# Eharvest.net
KiCad netlist of a schematic drawn in EAGLE
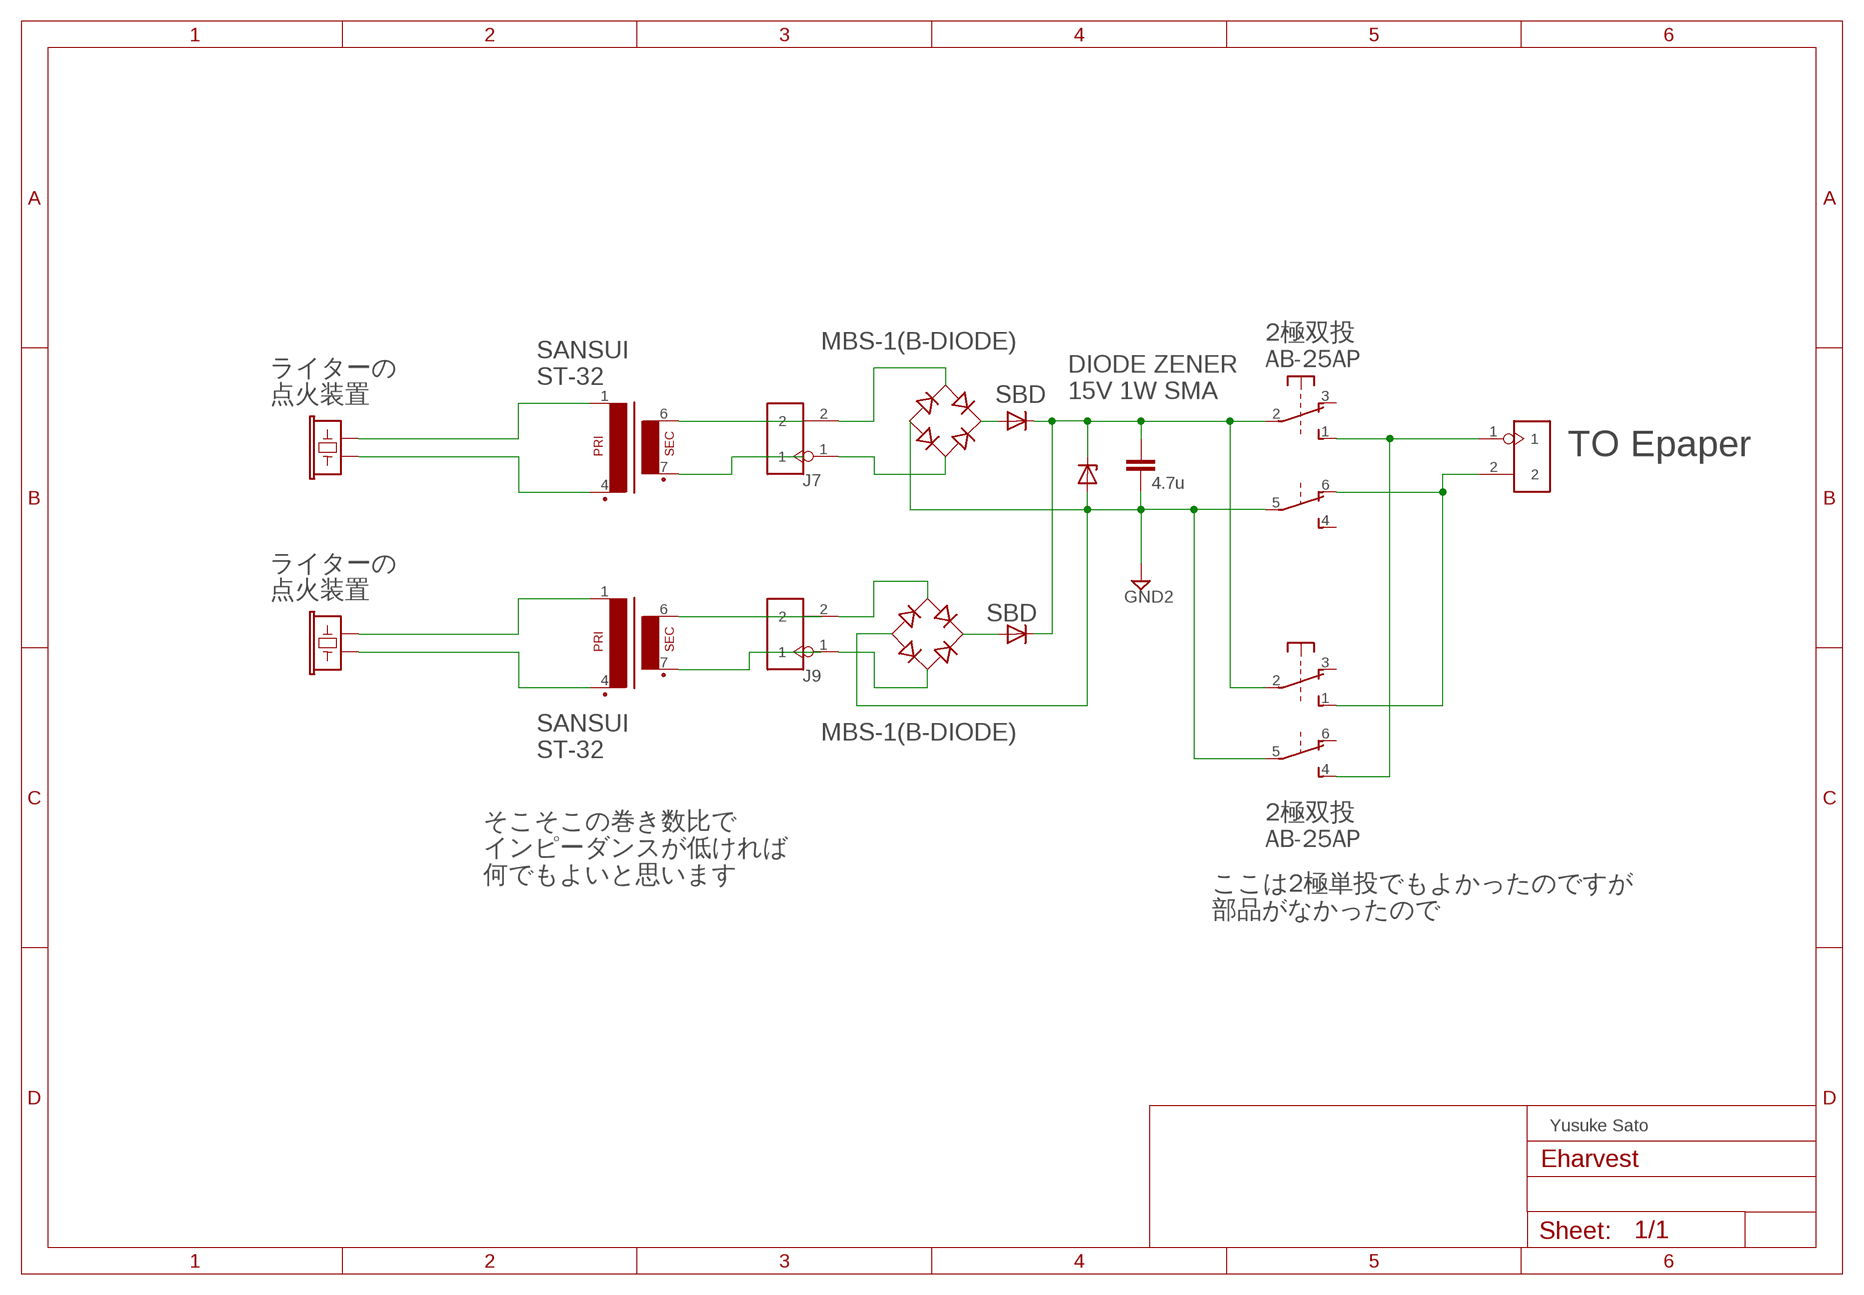
[diagram p0: schematic, sheet 1]

(export (version "E")
  (design (tool "Eeschema 10.0.6"))
  (components
    (comp (ref "C9")
      (value "4.7u")
      (footprint "eagle-import:C0402K")
      (libsource (lib "eagle-import") (part "C-EUC0402K"))
    )
    (comp (ref "D1")
      (value "1N4728")
      (footprint "eagle-import:DO41Z10")
      (libsource (lib "eagle-import") (part "1N4728"))
    )
    (comp (ref "D5")
      (value "MBS-1(B-DIODE)")
      (footprint "eagle-import:MBS-1(B-DIODE)")
      (libsource (lib "eagle-import") (part "MBS-1(B-DIODE)"))
    )
    (comp (ref "D7")
      (value "MBS-1(B-DIODE)")
      (footprint "eagle-import:MBS-1(B-DIODE)")
      (libsource (lib "eagle-import") (part "MBS-1(B-DIODE)"))
    )
    (comp (ref "D8")
      (value "DIODE-SOD123")
      (footprint "eagle-import:SOD123")
      (libsource (lib "eagle-import") (part "DIODE-SOD123"))
    )
    (comp (ref "D9")
      (value "DIODE-SOD123")
      (footprint "eagle-import:SOD123")
      (libsource (lib "eagle-import") (part "DIODE-SOD123"))
    )
    (comp (ref "J7")
      (value "HEADER-2P-65/35MIL")
      (footprint "eagle-import:2P-2.54-65_35MIL")
      (libsource (lib "eagle-import") (part "HEADER-2P-65/35MIL"))
    )
    (comp (ref "J8")
      (value "HEADER-2P-65/35MIL")
      (footprint "eagle-import:2P-2.54-65_35MIL")
      (libsource (lib "eagle-import") (part "HEADER-2P-65/35MIL"))
    )
    (comp (ref "J9")
      (value "HEADER-2P-65/35MIL")
      (footprint "eagle-import:2P-2.54-65_35MIL")
      (libsource (lib "eagle-import") (part "HEADER-2P-65/35MIL"))
    )
    (comp (ref "S1")
      (value "9450-2")
      (footprint "eagle-import:9450-2")
      (libsource (lib "eagle-import") (part "9450-2"))
    )
    (comp (ref "S3")
      (value "9450-2")
      (footprint "eagle-import:9450-2")
      (libsource (lib "eagle-import") (part "9450-2"))
    )
    (comp (ref "U$1")
      (value "BV20_1P1S")
      (footprint "eagle-import:BV20")
      (libsource (lib "eagle-import") (part "BV20_1P1S"))
    )
    (comp (ref "U$2")
      (value "BV20_1P1S")
      (footprint "eagle-import:BV20")
      (libsource (lib "eagle-import") (part "BV20_1P1S"))
    )
    (comp (ref "U$3")
      (value "MICELECTRET_SMD")
      (footprint "eagle-import:MIC_ELECTRET_SMD")
      (libsource (lib "eagle-import") (part "MICELECTRET_SMD"))
    )
    (comp (ref "U$4")
      (value "MICELECTRET_SMD")
      (footprint "eagle-import:MIC_ELECTRET_SMD")
      (libsource (lib "eagle-import") (part "MICELECTRET_SMD"))
    )
  )
  (nets
    (net (code "1") (name "GND2") (class "Default")
      (node (ref "C9") (pin "2") (pinfunction "2_2") (pintype "passive"))
      (node (ref "D1") (pin "A") (pinfunction "A_A") (pintype "passive"))
      (node (ref "D5") (pin "-") (pinfunction "-_-") (pintype "passive"))
      (node (ref "D7") (pin "-") (pinfunction "-_-") (pintype "passive"))
      (node (ref "S1") (pin "5") (pinfunction "P_5") (pintype "passive"))
      (node (ref "S3") (pin "5") (pinfunction "P_5") (pintype "passive"))
    )
    (net (code "2") (name "Net-(D5-AC1)") (class "Default")
      (node (ref "D5") (pin "~") (pinfunction "AC1_~") (pintype "passive"))
      (node (ref "J7") (pin "2") (pinfunction "2_2") (pintype "bidirectional"))
    )
    (net (code "3") (name "Net-(D5-AC2)") (class "Default")
      (node (ref "D5") (pin "~1") (pinfunction "AC2_~1") (pintype "passive"))
      (node (ref "J7") (pin "1") (pinfunction "1_1") (pintype "bidirectional"))
    )
    (net (code "4") (name "Net-(D5-Pad+)") (class "Default")
      (node (ref "D5") (pin "+") (pinfunction "+_+") (pintype "passive"))
      (node (ref "D8") (pin "A") (pinfunction "A_A") (pintype "passive"))
    )
    (net (code "5") (name "Net-(D7-AC1)") (class "Default")
      (node (ref "D7") (pin "~") (pinfunction "AC1_~") (pintype "passive"))
      (node (ref "J9") (pin "2") (pinfunction "2_2") (pintype "bidirectional"))
    )
    (net (code "6") (name "Net-(D7-AC2)") (class "Default")
      (node (ref "D7") (pin "~1") (pinfunction "AC2_~1") (pintype "passive"))
      (node (ref "J9") (pin "1") (pinfunction "1_1") (pintype "bidirectional"))
    )
    (net (code "7") (name "Net-(D7-Pad+)") (class "Default")
      (node (ref "D7") (pin "+") (pinfunction "+_+") (pintype "passive"))
      (node (ref "D9") (pin "A") (pinfunction "A_A") (pintype "passive"))
    )
    (net (code "8") (name "Net-(S1A-P)") (class "Default")
      (node (ref "C9") (pin "1") (pinfunction "1_1") (pintype "passive"))
      (node (ref "D1") (pin "C") (pinfunction "C_C") (pintype "passive"))
      (node (ref "D8") (pin "C") (pinfunction "C_C") (pintype "passive"))
      (node (ref "D9") (pin "C") (pinfunction "C_C") (pintype "passive"))
      (node (ref "S1") (pin "2") (pinfunction "P_2") (pintype "passive"))
      (node (ref "S3") (pin "2") (pinfunction "P_2") (pintype "passive"))
    )
    (net (code "9") (name "Net-(S1A-S)") (class "Default")
      (node (ref "J8") (pin "2") (pinfunction "2_2") (pintype "bidirectional"))
      (node (ref "S1") (pin "1") (pinfunction "S_1") (pintype "passive"))
      (node (ref "S3") (pin "6") (pinfunction "O_6") (pintype "passive"))
    )
    (net (code "10") (name "Net-(S1B-S)") (class "Default")
      (node (ref "J8") (pin "1") (pinfunction "1_1") (pintype "bidirectional"))
      (node (ref "S1") (pin "4") (pinfunction "S_4") (pintype "passive"))
      (node (ref "S3") (pin "1") (pinfunction "S_1") (pintype "passive"))
    )
    (net (code "11") (name "Net-(U$1-P1)") (class "Default")
      (node (ref "U$1") (pin "1") (pinfunction "P1_1") (pintype "passive"))
      (node (ref "U$3") (pin "2") (pinfunction "2_2") (pintype "passive"))
    )
    (net (code "12") (name "Net-(U$1-P2)") (class "Default")
      (node (ref "U$1") (pin "4") (pinfunction "P2_4") (pintype "passive"))
      (node (ref "U$3") (pin "1") (pinfunction "1_1") (pintype "passive"))
    )
    (net (code "13") (name "Net-(U$2-P1)") (class "Default")
      (node (ref "U$2") (pin "1") (pinfunction "P1_1") (pintype "passive"))
      (node (ref "U$4") (pin "2") (pinfunction "2_2") (pintype "passive"))
    )
    (net (code "14") (name "Net-(U$2-P2)") (class "Default")
      (node (ref "U$2") (pin "4") (pinfunction "P2_4") (pintype "passive"))
      (node (ref "U$4") (pin "1") (pinfunction "1_1") (pintype "passive"))
    )
    (net (code "15") (name "unconnected-(S1A-O-Pad3)") (class "Default")
      (node (ref "S1") (pin "3") (pinfunction "O_3") (pintype "passive"))
    )
    (net (code "16") (name "unconnected-(S1B-O-Pad6)") (class "Default")
      (node (ref "S1") (pin "6") (pinfunction "O_6") (pintype "passive"))
    )
    (net (code "17") (name "unconnected-(S3A-O-Pad3)") (class "Default")
      (node (ref "S3") (pin "3") (pinfunction "O_3") (pintype "passive"))
    )
    (net (code "18") (name "unconnected-(S3B-S-Pad4)") (class "Default")
      (node (ref "S3") (pin "4") (pinfunction "S_4") (pintype "passive"))
    )
    (net (code "19") (name "unconnected-(U$1-S3-Pad7)") (class "Default")
      (node (ref "U$1") (pin "7") (pinfunction "S3_7") (pintype "passive"))
    )
    (net (code "20") (name "unconnected-(U$1-S4-Pad6)") (class "Default")
      (node (ref "U$1") (pin "6") (pinfunction "S4_6") (pintype "passive"))
    )
    (net (code "21") (name "unconnected-(U$2-S3-Pad7)") (class "Default")
      (node (ref "U$2") (pin "7") (pinfunction "S3_7") (pintype "passive"))
    )
    (net (code "22") (name "unconnected-(U$2-S4-Pad6)") (class "Default")
      (node (ref "U$2") (pin "6") (pinfunction "S4_6") (pintype "passive"))
    )
  )
)
